# SENSORS_FMU_REV_1A.net
KiCad netlist of a schematic drawn in Altium Designer
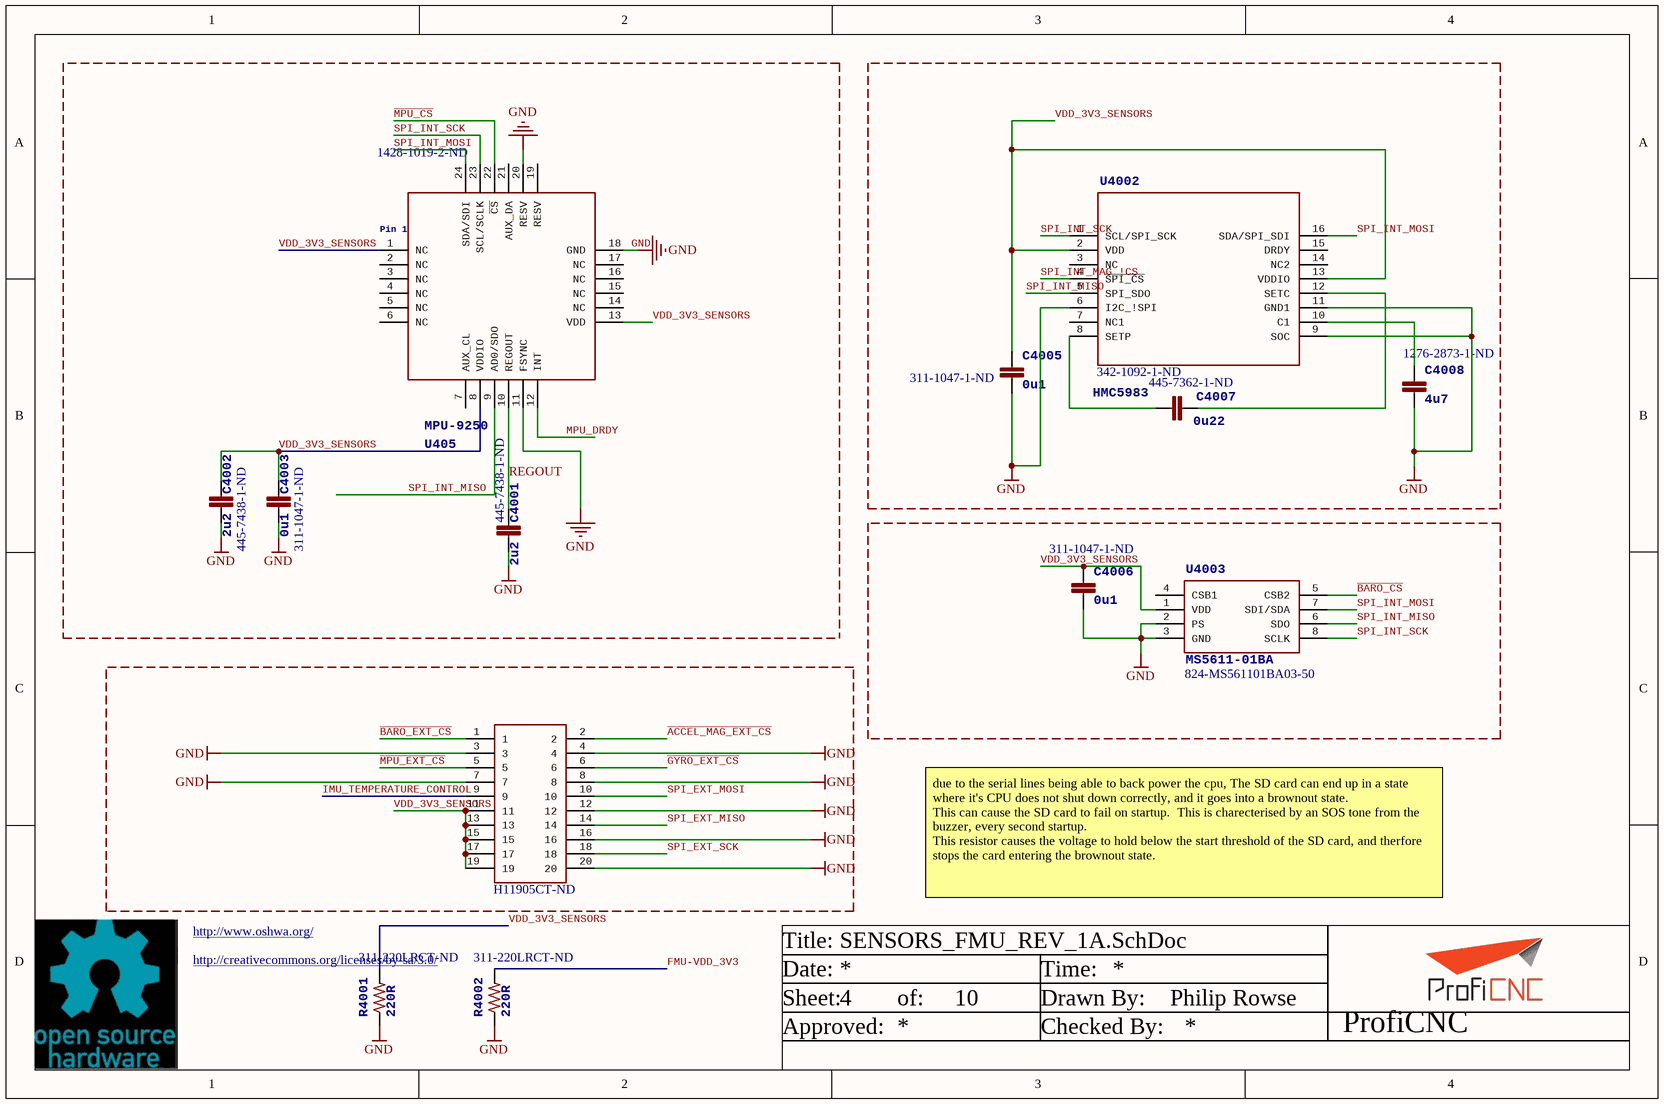
[diagram p0: SENSORS_FMU_REV_1A.SchDoc]

(export (version "E")
  (design (tool "Eeschema 10.0.6"))
  (components
    (comp (ref "C4001")
      (value "2u2")
      (footprint "0603-CAP")
      (description "CAP CER 2.2UF 16V 10% X6S 0603")
      (fields
        (field (name "PARTNO") "C1608X6S1C225K080AC")
        (field (name "SUPPLIER PART NUMBER 1") "445-7438-1-ND")
        (field (name "3DR_PARTNO") "ECM0619")
      )
      (libsource (lib "pixhawk2") (part "CAP0603"))
    )
    (comp (ref "C4002")
      (value "2u2")
      (footprint "0603-CAP")
      (description "CAP CER 2.2UF 16V 10% X6S 0603")
      (fields
        (field (name "PARTNO") "C1608X6S1C225K080AC")
        (field (name "SUPPLIER PART NUMBER 1") "445-7438-1-ND")
        (field (name "3DR_PARTNO") "ECM0619")
      )
      (libsource (lib "pixhawk2") (part "CAP0603"))
    )
    (comp (ref "C4003")
      (value "0u1")
      (footprint "0402-CAP")
      (description "CAP CER 0.1UF 16V Y5V 0402")
      (fields
        (field (name "PARTNO") "CC0402ZRY5V7BB104")
        (field (name "SUPPLIER PART NUMBER 1") "311-1047-1-ND")
        (field (name "3DR_PARTNO") "ECM0700")
      )
      (libsource (lib "pixhawk2") (part "CAP0402"))
    )
    (comp (ref "C4005")
      (value "0u1")
      (footprint "0402-CAP")
      (description "CAP CER 0.1UF 16V Y5V 0402")
      (fields
        (field (name "SUPPLIER PART NUMBER 1") "311-1047-1-ND")
        (field (name "3DR_PARTNO") "ECM0700")
        (field (name "PARTNO") "CC0402ZRY5V7BB104")
      )
      (libsource (lib "pixhawk2") (part "CAP0402"))
    )
    (comp (ref "C4006")
      (value "0u1")
      (footprint "0402-CAP")
      (description "CAP CER 0.1UF 16V Y5V 0402")
      (fields
        (field (name "PARTNO") "CC0402ZRY5V7BB104")
        (field (name "SUPPLIER PART NUMBER 1") "311-1047-1-ND")
        (field (name "3DR_PARTNO") "ECM0700")
      )
      (libsource (lib "pixhawk2") (part "CAP0402"))
    )
    (comp (ref "C4007")
      (value "0u22")
      (footprint "0402-CAP")
      (description "CAP CER 0.22UF 25V 10% X7R 0402")
      (fields
        (field (name "3DR_PARTNO") "ECM")
        (field (name "PARTNO") "C1005X6S1E224K050BC")
        (field (name "SUPPLIER PART NUMBER 1") "445-7362-1-ND")
      )
      (libsource (lib "") (part "CAP0402_1"))
    )
    (comp (ref "C4008")
      (value "4u7")
      (footprint "0805")
      (description "CAP CER 4.7UF 16V 10% X7R 0805")
      (fields
        (field (name "PARTNO") "CL21B475KOFNNNE")
        (field (name "SUPPLIER PART NUMBER 1") "1276-2873-1-ND")
        (field (name "3DR_PARTNO") "ECM0622")
      )
      (libsource (lib "pixhawk2") (part "CAP0805"))
    )
    (comp (ref "R4001")
      (value "220R")
      (footprint "0402-RES")
      (description "RES 220 OHM 1/16W 1% 0402 SMD")
      (fields
        (field (name "SUPPLIER PART NUMBER 1") "311-220LRCT-ND")
        (field (name "3DR_PARTNO") "ECM0821")
        (field (name "PARTNO") "RC0402FR-07220RL")
      )
      (libsource (lib "pixhawk2") (part "RESISTOR0402-RES"))
    )
    (comp (ref "R4002")
      (value "220R")
      (footprint "0402-RES")
      (description "RES 220 OHM 1/16W 1% 0402 SMD")
      (fields
        (field (name "SUPPLIER PART NUMBER 1") "311-220LRCT-ND")
        (field (name "3DR_PARTNO") "ECM0821")
        (field (name "PARTNO") "RC0402FR-07220RL")
      )
      (libsource (lib "pixhawk2") (part "RESISTOR0402-RES"))
    )
    (comp (ref "U$2")
      (value "DF40C-20-DS")
      (footprint "DF-40C-20DS")
      (description "CONN RCPT 20POS 0.4MM SMD GOLD")
      (fields
        (field (name "SUPPLIER PART NUMBER 1") "H11905CT-ND")
        (field (name "3DR_PARTNO") "ECM0517")
        (field (name "PARTNO") "DF40C(2.0)-20DS-0.4V(51)")
      )
      (libsource (lib "pixhawk2") (part "DF40C-20-DS"))
    )
    (comp (ref "U405")
      (value "MPU-9250")
      (footprint "MPU-9250")
      (fields (field (name "PIN 1") "Pin 1") (field (name "SUPPLIER PART NUMBER 1") "1428-1019-2-ND"))
      (libsource (lib "pixhawk2") (part "MPU-6500"))
    )
    (comp (ref "U4002")
      (value "HMC5983")
      (footprint "HMC5983-new")
      (description "IC COMPASS 3 AXIS 16-LCC")
      (fields (field (name "SUPPLIER PART NUMBER 1") "342-1092-1-ND") (field (name "3DR_PARTNO") "ECM0672"))
      (libsource (lib "pixhawk2") (part "HMC5983"))
    )
    (comp (ref "U4003")
      (value "MS5611-01BA")
      (footprint "MS5611-01BA")
      (description "Board Mount Pressure Sensors")
      (fields
        (field (name "SUPPLIER PART NUMBER 1") "824-MS561101BA03-50")
        (field (name "3DR_PARTNO") "ECM0835")
      )
      (libsource (lib "pixhawk2") (part "MS5611-01BA"))
    )
  )
  (nets
    (net (code "1") (name "/FMU-VDD_3V3") (class "Default")
      (node (ref "R4002") (pin "P$2") (pinfunction "2_P$2") (pintype "passive"))
    )
    (net (code "2") (name "/IMU_TEMPERATURE_CONTROL") (class "Default")
      (node (ref "U$2") (pin "9") (pinfunction "9_9") (pintype "passive"))
    )
    (net (code "3") (name "/MPU_DRDY") (class "Default")
      (node (ref "U405") (pin "12") (pinfunction "INT_12") (pintype "passive"))
    )
    (net (code "4") (name "/REGOUT") (class "Default")
      (node (ref "C4001") (pin "P$1") (pinfunction "1_P$1") (pintype "passive"))
      (node (ref "U405") (pin "10") (pinfunction "REGOUT_10") (pintype "passive"))
    )
    (net (code "5") (name "/SPI_EXT_MISO") (class "Default")
      (node (ref "U$2") (pin "14") (pinfunction "14_14") (pintype "passive"))
    )
    (net (code "6") (name "/SPI_EXT_MOSI") (class "Default")
      (node (ref "U$2") (pin "10") (pinfunction "10_10") (pintype "passive"))
    )
    (net (code "7") (name "/SPI_EXT_SCK") (class "Default")
      (node (ref "U$2") (pin "18") (pinfunction "18_18") (pintype "passive"))
    )
    (net (code "8") (name "/SPI_INT_MAG_!CS") (class "Default")
      (node (ref "U4002") (pin "4") (pinfunction "~{SPI_CS}_4") (pintype "passive"))
    )
    (net (code "9") (name "/SPI_INT_MISO") (class "Default")
      (node (ref "U4002") (pin "5") (pinfunction "SPI_SDO_5") (pintype "passive"))
      (node (ref "U4003") (pin "6") (pinfunction "SDO_6") (pintype "passive"))
      (node (ref "U405") (pin "9") (pinfunction "AD0/SDO_9") (pintype "passive"))
    )
    (net (code "10") (name "/SPI_INT_MOSI") (class "Default")
      (node (ref "U4002") (pin "16") (pinfunction "SDA/SPI_SDI_16") (pintype "passive"))
      (node (ref "U4003") (pin "7") (pinfunction "SDI/SDA_7") (pintype "passive"))
      (node (ref "U405") (pin "24") (pinfunction "SDA/SDI_24") (pintype "passive"))
    )
    (net (code "11") (name "/SPI_INT_SCK") (class "Default")
      (node (ref "U4002") (pin "1") (pinfunction "SCL/SPI_SCK_1") (pintype "passive"))
      (node (ref "U4003") (pin "8") (pinfunction "SCLK_8") (pintype "passive"))
      (node (ref "U405") (pin "23") (pinfunction "SCL/SCLK_23") (pintype "passive"))
    )
    (net (code "12") (name "/VDD_3V3_SENSORS") (class "Default")
      (node (ref "C4002") (pin "P$1") (pinfunction "1_P$1") (pintype "passive"))
      (node (ref "C4003") (pin "P$1") (pinfunction "1_P$1") (pintype "passive"))
      (node (ref "C4005") (pin "P$1") (pinfunction "1_P$1") (pintype "passive"))
      (node (ref "C4006") (pin "P$1") (pinfunction "1_P$1") (pintype "passive"))
      (node (ref "R4001") (pin "P$2") (pinfunction "2_P$2") (pintype "passive"))
      (node (ref "U$2") (pin "11") (pinfunction "11_11") (pintype "passive"))
      (node (ref "U$2") (pin "13") (pinfunction "13_13") (pintype "passive"))
      (node (ref "U$2") (pin "15") (pinfunction "15_15") (pintype "passive"))
      (node (ref "U$2") (pin "17") (pinfunction "17_17") (pintype "passive"))
      (node (ref "U$2") (pin "19") (pinfunction "19_19") (pintype "passive"))
      (node (ref "U4002") (pin "13") (pinfunction "VDDIO_13") (pintype "power_in"))
      (node (ref "U4002") (pin "2") (pinfunction "VDD_2") (pintype "power_in"))
      (node (ref "U4003") (pin "1") (pinfunction "VDD_1") (pintype "passive"))
      (node (ref "U405") (pin "1") (pinfunction "NC_1") (pintype "passive"))
      (node (ref "U405") (pin "13") (pinfunction "VDD_13") (pintype "passive"))
      (node (ref "U405") (pin "8") (pinfunction "VDDIO_8") (pintype "passive"))
    )
    (net (code "13") (name "/~{ACCEL_MAG_EXT_CS}") (class "Default")
      (node (ref "U$2") (pin "2") (pinfunction "2_2") (pintype "passive"))
    )
    (net (code "14") (name "/~{BARO_CS}") (class "Default")
      (node (ref "U4003") (pin "5") (pinfunction "CSB2_5") (pintype "passive"))
    )
    (net (code "15") (name "/~{BARO_EXT_CS}") (class "Default")
      (node (ref "U$2") (pin "1") (pinfunction "1_1") (pintype "passive"))
    )
    (net (code "16") (name "/~{GYRO_EXT_CS}") (class "Default")
      (node (ref "U$2") (pin "6") (pinfunction "6_6") (pintype "passive"))
    )
    (net (code "17") (name "/~{MPU_CS}") (class "Default")
      (node (ref "U405") (pin "22") (pinfunction "~{CS}_22") (pintype "passive"))
    )
    (net (code "18") (name "/~{MPU_EXT_CS}") (class "Default")
      (node (ref "U$2") (pin "5") (pinfunction "5_5") (pintype "passive"))
    )
    (net (code "19") (name "GND") (class "Default")
      (node (ref "C4001") (pin "P$2") (pinfunction "2_P$2") (pintype "passive"))
      (node (ref "C4002") (pin "P$2") (pinfunction "2_P$2") (pintype "passive"))
      (node (ref "C4003") (pin "P$2") (pinfunction "2_P$2") (pintype "passive"))
      (node (ref "C4005") (pin "P$2") (pinfunction "2_P$2") (pintype "passive"))
      (node (ref "C4006") (pin "P$2") (pinfunction "2_P$2") (pintype "passive"))
      (node (ref "C4008") (pin "2") (pinfunction "2_2") (pintype "passive"))
      (node (ref "R4001") (pin "P$1") (pinfunction "1_P$1") (pintype "passive"))
      (node (ref "R4002") (pin "P$1") (pinfunction "1_P$1") (pintype "passive"))
      (node (ref "U$2") (pin "12") (pinfunction "12_12") (pintype "passive"))
      (node (ref "U$2") (pin "16") (pinfunction "16_16") (pintype "passive"))
      (node (ref "U$2") (pin "20") (pinfunction "20_20") (pintype "passive"))
      (node (ref "U$2") (pin "3") (pinfunction "3_3") (pintype "passive"))
      (node (ref "U$2") (pin "4") (pinfunction "4_4") (pintype "passive"))
      (node (ref "U$2") (pin "7") (pinfunction "7_7") (pintype "passive"))
      (node (ref "U$2") (pin "8") (pinfunction "8_8") (pintype "passive"))
      (node (ref "U4002") (pin "11") (pinfunction "GND1_11") (pintype "passive"))
      (node (ref "U4002") (pin "6") (pinfunction "I2C_!SPI_6") (pintype "passive"))
      (node (ref "U4002") (pin "9") (pinfunction "SOC_9") (pintype "passive"))
      (node (ref "U4003") (pin "2") (pinfunction "PS_2") (pintype "passive"))
      (node (ref "U4003") (pin "3") (pinfunction "GND_3") (pintype "passive"))
      (node (ref "U405") (pin "11") (pinfunction "FSYNC_11") (pintype "passive"))
      (node (ref "U405") (pin "18") (pinfunction "GND_18") (pintype "passive"))
      (node (ref "U405") (pin "20") (pinfunction "RESV_20") (pintype "passive"))
    )
    (net (code "20") (name "Net-(C4007-1)") (class "Default")
      (node (ref "C4007") (pin "P$1") (pinfunction "1_P$1") (pintype "passive"))
      (node (ref "U4002") (pin "12") (pinfunction "SETC_12") (pintype "passive"))
    )
    (net (code "21") (name "Net-(C4007-2)") (class "Default")
      (node (ref "C4007") (pin "P$2") (pinfunction "2_P$2") (pintype "passive"))
      (node (ref "U4002") (pin "8") (pinfunction "SETP_8") (pintype "passive"))
    )
    (net (code "22") (name "Net-(U4002-C1)") (class "Default")
      (node (ref "C4008") (pin "1") (pinfunction "1_1") (pintype "passive"))
      (node (ref "U4002") (pin "10") (pinfunction "C1_10") (pintype "passive"))
    )
    (net (code "23") (name "unconnected-(U405-AUX_CL-Pad7)") (class "Default")
      (node (ref "U405") (pin "7") (pinfunction "AUX_CL_7") (pintype "passive"))
    )
    (net (code "24") (name "unconnected-(U405-AUX_DA-Pad21)") (class "Default")
      (node (ref "U405") (pin "21") (pinfunction "AUX_DA_21") (pintype "passive"))
    )
    (net (code "25") (name "unconnected-(U405-NC-Pad2)") (class "Default")
      (node (ref "U405") (pin "2") (pinfunction "NC_2") (pintype "passive"))
    )
    (net (code "26") (name "unconnected-(U405-NC-Pad3)") (class "Default")
      (node (ref "U405") (pin "3") (pinfunction "NC_3") (pintype "passive"))
    )
    (net (code "27") (name "unconnected-(U405-NC-Pad4)") (class "Default")
      (node (ref "U405") (pin "4") (pinfunction "NC_4") (pintype "passive"))
    )
    (net (code "28") (name "unconnected-(U405-NC-Pad5)") (class "Default")
      (node (ref "U405") (pin "5") (pinfunction "NC_5") (pintype "passive"))
    )
    (net (code "29") (name "unconnected-(U405-NC-Pad6)") (class "Default")
      (node (ref "U405") (pin "6") (pinfunction "NC_6") (pintype "passive"))
    )
    (net (code "30") (name "unconnected-(U405-NC-Pad14)") (class "Default")
      (node (ref "U405") (pin "14") (pinfunction "NC_14") (pintype "passive"))
    )
    (net (code "31") (name "unconnected-(U405-NC-Pad15)") (class "Default")
      (node (ref "U405") (pin "15") (pinfunction "NC_15") (pintype "passive"))
    )
    (net (code "32") (name "unconnected-(U405-NC-Pad16)") (class "Default")
      (node (ref "U405") (pin "16") (pinfunction "NC_16") (pintype "passive"))
    )
    (net (code "33") (name "unconnected-(U405-NC-Pad17)") (class "Default")
      (node (ref "U405") (pin "17") (pinfunction "NC_17") (pintype "passive"))
    )
    (net (code "34") (name "unconnected-(U405-RESV-Pad19)") (class "Default")
      (node (ref "U405") (pin "19") (pinfunction "RESV_19") (pintype "passive"))
    )
    (net (code "35") (name "unconnected-(U4002-DRDY-Pad15)") (class "Default")
      (node (ref "U4002") (pin "15") (pinfunction "DRDY_15") (pintype "passive"))
    )
    (net (code "36") (name "unconnected-(U4002-NC-Pad3)") (class "Default")
      (node (ref "U4002") (pin "3") (pinfunction "NC_3") (pintype "passive"))
    )
    (net (code "37") (name "unconnected-(U4002-NC1-Pad7)") (class "Default")
      (node (ref "U4002") (pin "7") (pinfunction "NC1_7") (pintype "passive"))
    )
    (net (code "38") (name "unconnected-(U4002-NC2-Pad14)") (class "Default")
      (node (ref "U4002") (pin "14") (pinfunction "NC2_14") (pintype "passive"))
    )
    (net (code "39") (name "unconnected-(U4003-CSB1-Pad4)") (class "Default")
      (node (ref "U4003") (pin "4") (pinfunction "CSB1_4") (pintype "passive"))
    )
  )
)
